# AIRZAI_LED_SENSE_FLEX_REVA.net
KiCad netlist of a schematic drawn in Altium Designer
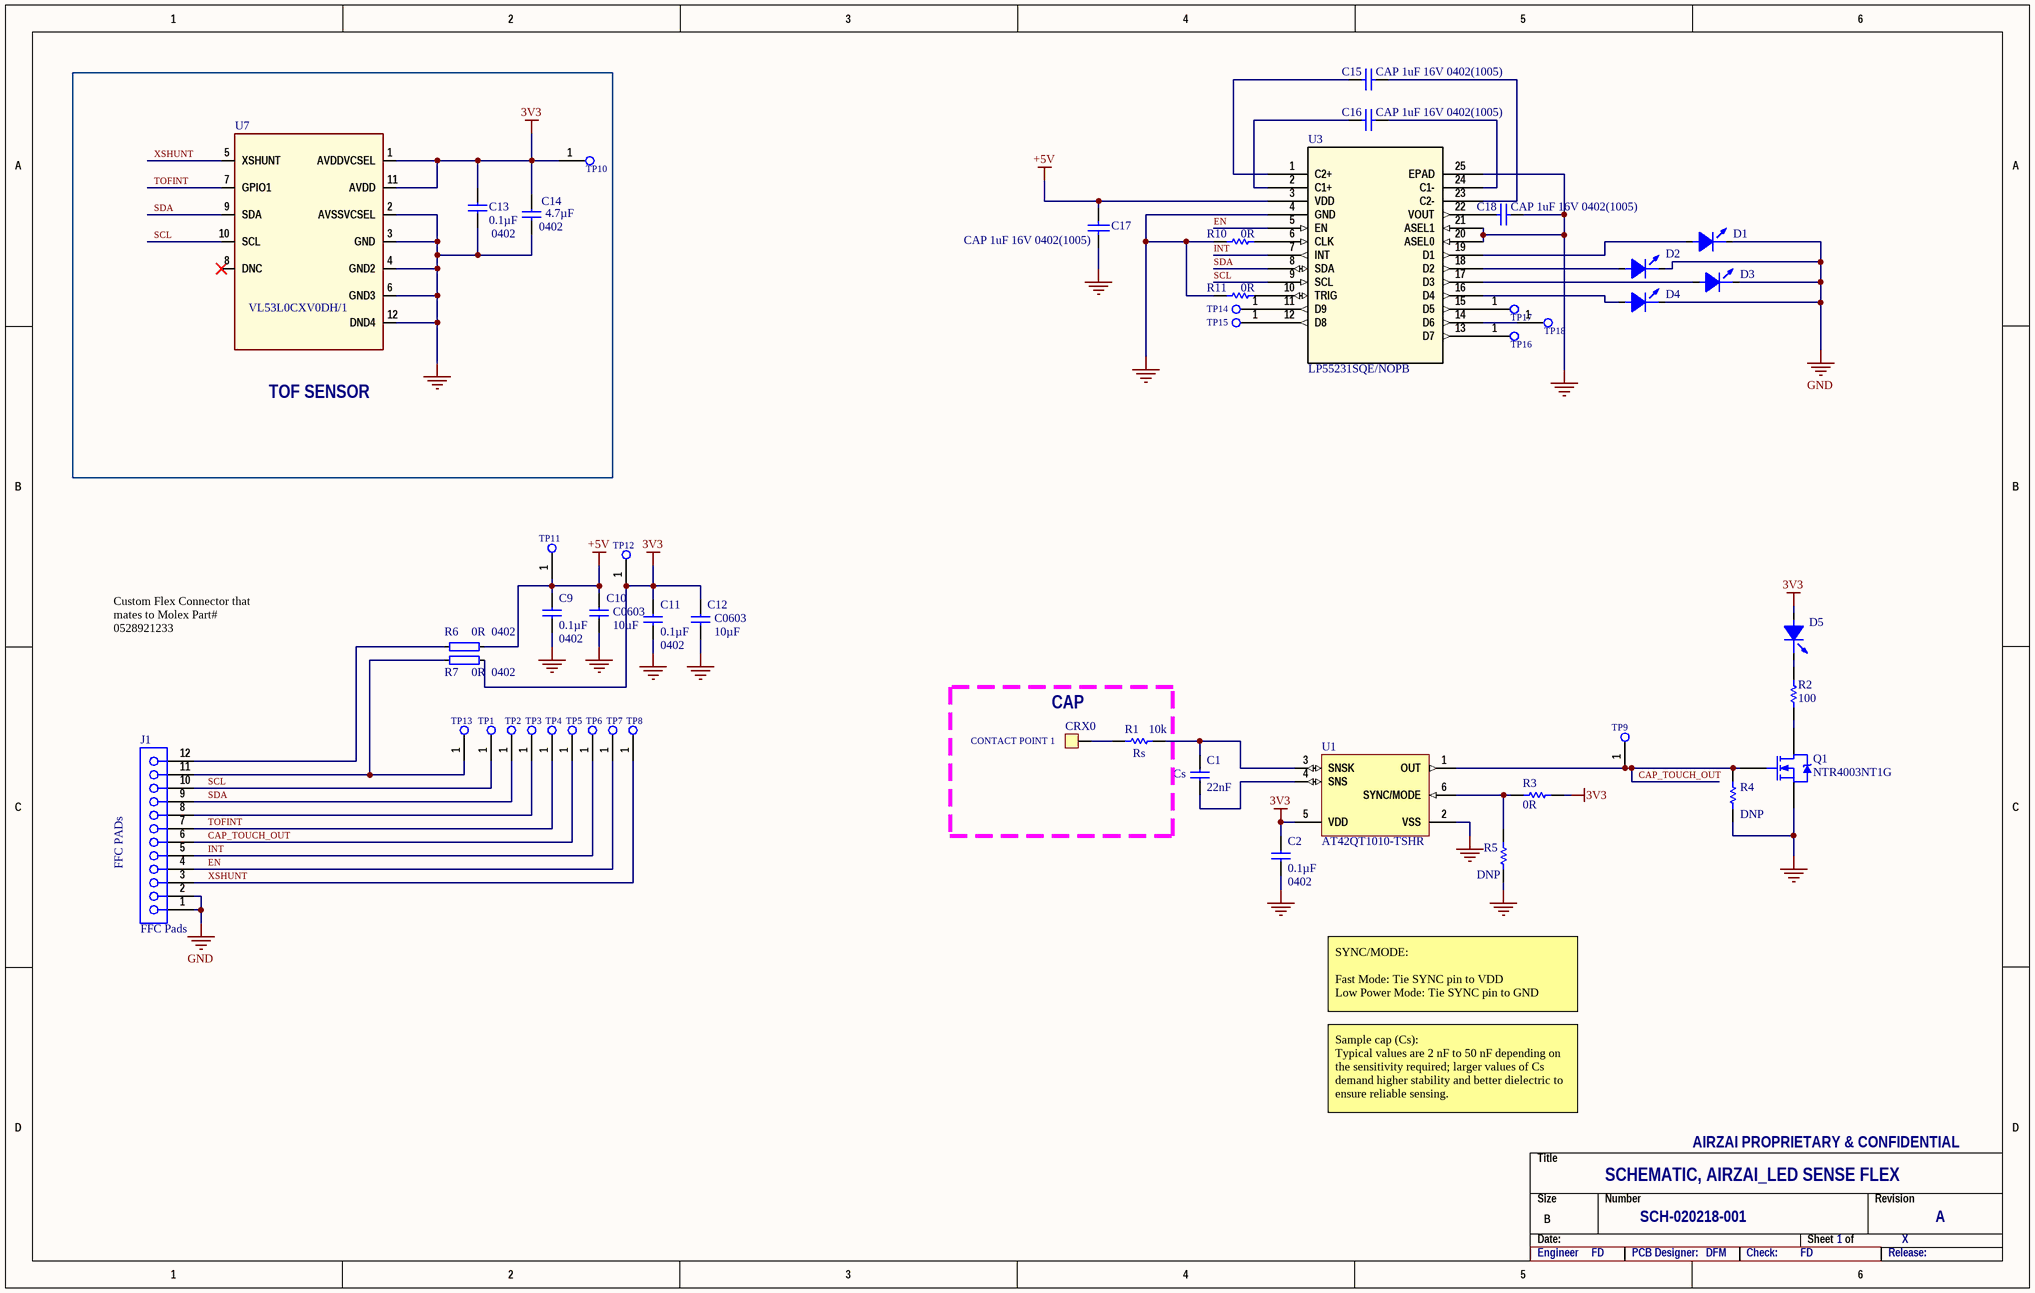
[diagram p0: AIRZAI_LED_SENSE_FLEX_REVA.SchDoc]

(export (version "E")
  (design (tool "Eeschema 10.0.6"))
  (components
    (comp (ref "C1")
      (value "22nF")
      (footprint "0402CAP")
      (description "Capacitor, X7R, ±10%")
      (fields
        (field (name "MANUFACTURER") "TDK")
        (field (name "MANUFACTURER PART NUMBER") "CGA2B2X7R1E223K050BA")
      )
      (libsource (lib "Nordic Passive DB") (part "CAP"))
    )
    (comp (ref "C2")
      (value "0.1µF")
      (footprint "0402")
      (description "Capacitor, X7R, ±10%")
      (fields (field (name "MANUFACTURER") "TDK") (field (name "MANUFACTURER PART NUMBER") "C1005X7R1C104K"))
      (libsource (lib "Nordic Passive DB") (part "CAP"))
    )
    (comp (ref "C9")
      (value "0.1µF")
      (footprint "0402")
      (description "Capacitor, X7R, ±10%")
      (fields (field (name "MANUFACTURER") "TDK") (field (name "MANUFACTURER PART NUMBER") "C1005X7R1C104K"))
      (libsource (lib "Nordic Passive DB") (part "CAP"))
    )
    (comp (ref "C10")
      (value "10µF")
      (footprint "C0603")
      (description "Capacitor, X7R, ±10%")
      (fields
        (field (name "MANUFACTURER") "MURATA")
        (field (name "MANUFACTURER PART NUMBER") "GRM188R60J106ME47D")
      )
      (libsource (lib "Nordic Passive DB") (part "CAP"))
    )
    (comp (ref "C11")
      (value "0.1µF")
      (footprint "0402")
      (description "Capacitor, X7R, ±10%")
      (fields (field (name "MANUFACTURER") "TDK") (field (name "MANUFACTURER PART NUMBER") "C1005X7R1C104K"))
      (libsource (lib "Nordic Passive DB") (part "CAP"))
    )
    (comp (ref "C12")
      (value "10µF")
      (footprint "C0603")
      (description "Capacitor, X7R, ±10%")
      (fields
        (field (name "MANUFACTURER") "MURATA")
        (field (name "MANUFACTURER PART NUMBER") "GRM188R60J106ME47D")
      )
      (libsource (lib "Nordic Passive DB") (part "CAP"))
    )
    (comp (ref "C13")
      (value "0.1µF")
      (footprint "0402")
      (description "Capacitor, X7R, ±10%")
      (fields (field (name "MANUFACTURER") "TDK") (field (name "MANUFACTURER PART NUMBER") "C1005X7R1C104K"))
      (libsource (lib "Nordic Passive DB") (part "CAP"))
    )
    (comp (ref "C14")
      (value "4.7µF")
      (footprint "0402")
      (description "Capacitor, X7R, ±10%")
      (fields (field (name "MANUFACTURER") "TDK") (field (name "MANUFACTURER PART NUMBER") "C1005X5R0J475M"))
      (libsource (lib "Nordic Passive DB") (part "CAP"))
    )
    (comp (ref "C15")
      (value "CAP 1uF 16V 0402(1005)")
      (footprint "CAPC0402(1005)60_M")
      (description "CAP 1uF 16V ±10% 0402 (1005 Metric) Thickness 0.6mm SMD")
      (fields (field (name "TOLERANCE") "Â±10%") (field (name "MANUFACTURER") "Taiyo Yuden"))
      (libsource (lib "AIRZAI_LED_SENSE_FLEX_REVA") (part "CAP"))
    )
    (comp (ref "C16")
      (value "CAP 1uF 16V 0402(1005)")
      (footprint "CAPC0402(1005)60_M")
      (description "CAP 1uF 16V ±10% 0402 (1005 Metric) Thickness 0.6mm SMD")
      (fields (field (name "TOLERANCE") "Â±10%") (field (name "MANUFACTURER") "Taiyo Yuden"))
      (libsource (lib "AIRZAI_LED_SENSE_FLEX_REVA") (part "CAP"))
    )
    (comp (ref "C17")
      (value "CAP 1uF 16V 0402(1005)")
      (footprint "CAPC0402(1005)60_M")
      (description "CAP 1uF 16V ±10% 0402 (1005 Metric) Thickness 0.6mm SMD")
      (fields (field (name "TOLERANCE") "Â±10%") (field (name "MANUFACTURER") "Taiyo Yuden"))
      (libsource (lib "AIRZAI_LED_SENSE_FLEX_REVA") (part "CAP"))
    )
    (comp (ref "C18")
      (value "CAP 1uF 16V 0402(1005)")
      (footprint "CAPC0402(1005)60_M")
      (description "CAP 1uF 16V ±10% 0402 (1005 Metric) Thickness 0.6mm SMD")
      (fields (field (name "TOLERANCE") "Â±10%") (field (name "MANUFACTURER") "Taiyo Yuden"))
      (libsource (lib "AIRZAI_LED_SENSE_FLEX_REVA") (part "CAP"))
    )
    (comp (ref "CRX0")
      (value "CONTACT POINT 1")
      (footprint "CONTACT_POINT_1CM _SQ")
      (libsource (lib "AIRZAI_LED_SENSE_FLEX_REVA") (part "WIRE_POINT"))
    )
    (comp (ref "D1")
      (value "WHITE")
      (footprint "LED1206_LTW-C230DS")
      (fields (field (name "MANUFACTURER PART NUMBER") "LTW-C230DS") (field (name "MANUFACTURER") "LITEON"))
      (libsource (lib "AIRZAI_LED_SENSE_FLEX_REVA") (part "LED_LTW-C230DS"))
    )
    (comp (ref "D2")
      (value "WHITE")
      (footprint "LED1206_LTW-C230DS")
      (fields (field (name "MANUFACTURER PART NUMBER") "LTW-C230DS") (field (name "MANUFACTURER") "LITEON"))
      (libsource (lib "AIRZAI_LED_SENSE_FLEX_REVA") (part "LED_LTW-C230DS"))
    )
    (comp (ref "D3")
      (value "WHITE")
      (footprint "LED1206_LTW-C230DS")
      (fields (field (name "MANUFACTURER PART NUMBER") "LTW-C230DS") (field (name "MANUFACTURER") "LITEON"))
      (libsource (lib "AIRZAI_LED_SENSE_FLEX_REVA") (part "LED_LTW-C230DS"))
    )
    (comp (ref "D4")
      (value "WHITE")
      (footprint "LED1206_LTW-C230DS")
      (fields (field (name "MANUFACTURER PART NUMBER") "LTW-C230DS") (field (name "MANUFACTURER") "LITEON"))
      (libsource (lib "AIRZAI_LED_SENSE_FLEX_REVA") (part "LED_LTW-C230DS"))
    )
    (comp (ref "D5")
      (value "WHITE")
      (footprint "LED1206_LTW-C230DS")
      (fields (field (name "MANUFACTURER PART NUMBER") "LTW-C230DS") (field (name "MANUFACTURER") "LITEON"))
      (libsource (lib "AIRZAI_LED_SENSE_FLEX_REVA") (part "LED_LTW-C230DS"))
    )
    (comp (ref "J1")
      (value "FFC Pads")
      (footprint "FFC_Pads")
      (description "0.5 mm Pitch FFC Pads")
      (libsource (lib "AIRZAI_LED_SENSE_FLEX_REVA") (part "FFC_PADS"))
    )
    (comp (ref "Q1")
      (value "NTR4003NT1G")
      (footprint "TO-220AB")
      (description "MOSFET N-CH 30V 500MA SOT-23")
      (fields (field (name "MANUFACTURER") "ON Semiconductor"))
      (libsource (lib "Miscellaneous Devices") (part "NMOS-2"))
    )
    (comp (ref "R1")
      (value "10k")
      (footprint "0402")
      (description "10k 0.063W 1% 0402 (1005 Metric)  SMD")
      (fields (field (name "TOLERANCE") "None") (field (name "POWER") "0.063W"))
      (libsource (lib "AIRZAI_LED_SENSE_FLEX_REVA") (part "RES"))
    )
    (comp (ref "R2")
      (value "100")
      (footprint "0402")
      (description "100 0.063W 1% 0402 (1005 Metric)  SMD")
      (fields (field (name "TOLERANCE") "None") (field (name "MANUFACTURER") "Yageo"))
      (libsource (lib "AIRZAI_LED_SENSE_FLEX_REVA") (part "RES"))
    )
    (comp (ref "R3")
      (value "0R")
      (footprint "0402")
      (description "Jumper 0402 (1005 Metric)")
      (fields (field (name "TOLERANCE") "None") (field (name "MANUFACTURER") "Panasonic"))
      (libsource (lib "AIRZAI_LED_SENSE_FLEX_REVA") (part "RES"))
    )
    (comp (ref "R4")
      (value "DNP")
      (footprint "0402")
      (fields
        (field (name "TOLERANCE") "None")
        (field (name "POWER") "0.0625 W")
        (field (name "Comment") "DNP 0402(1005)")
      )
      (libsource (lib "AIRZAI_LED_SENSE_FLEX_REVA") (part "RES"))
    )
    (comp (ref "R5")
      (value "DNP")
      (footprint "0402")
      (fields
        (field (name "TOLERANCE") "None")
        (field (name "POWER") "0.0625 W")
        (field (name "Comment") "DNP 0402(1005)")
      )
      (libsource (lib "AIRZAI_LED_SENSE_FLEX_REVA") (part "RES"))
    )
    (comp (ref "R6")
      (value "0R")
      (footprint "0402")
      (description "Resistor, ±1%, 0.063W")
      (fields
        (field (name "MANUFACTURER") "Panasonic")
        (field (name "MANUFACTURER PART NUMBER") "ERJ-2GE0R00X")
      )
      (libsource (lib "Nordic Passive DB") (part "RES_1"))
    )
    (comp (ref "R7")
      (value "0R")
      (footprint "0402")
      (description "Resistor, ±1%, 0.063W")
      (fields
        (field (name "MANUFACTURER") "Panasonic")
        (field (name "MANUFACTURER PART NUMBER") "ERJ-2GE0R00X")
      )
      (libsource (lib "Nordic Passive DB") (part "RES_1"))
    )
    (comp (ref "R10")
      (value "0R")
      (footprint "0402")
      (description "Jumper 0402 (1005 Metric)")
      (fields (field (name "TOLERANCE") "None") (field (name "MANUFACTURER") "Panasonic"))
      (libsource (lib "AIRZAI_LED_SENSE_FLEX_REVA") (part "RES"))
    )
    (comp (ref "R11")
      (value "0R")
      (footprint "0402")
      (description "Jumper 0402 (1005 Metric)")
      (fields (field (name "TOLERANCE") "None") (field (name "MANUFACTURER") "Panasonic"))
      (libsource (lib "AIRZAI_LED_SENSE_FLEX_REVA") (part "RES"))
    )
    (comp (ref "TP1")
      (value "Test Point")
      (footprint "TP_0.9MM")
      (libsource (lib "AIRZAI_LED_SENSE_FLEX_REVA") (part "Test Point"))
    )
    (comp (ref "TP2")
      (value "Test Point")
      (footprint "TP_0.9MM")
      (libsource (lib "AIRZAI_LED_SENSE_FLEX_REVA") (part "Test Point"))
    )
    (comp (ref "TP3")
      (value "Test Point")
      (footprint "TP_0.9MM")
      (libsource (lib "AIRZAI_LED_SENSE_FLEX_REVA") (part "Test Point"))
    )
    (comp (ref "TP4")
      (value "Test Point")
      (footprint "TP_0.9MM")
      (libsource (lib "AIRZAI_LED_SENSE_FLEX_REVA") (part "Test Point"))
    )
    (comp (ref "TP5")
      (value "Test Point")
      (footprint "TP_0.9MM")
      (libsource (lib "AIRZAI_LED_SENSE_FLEX_REVA") (part "Test Point"))
    )
    (comp (ref "TP6")
      (value "Test Point")
      (footprint "TP_0.9MM")
      (libsource (lib "AIRZAI_LED_SENSE_FLEX_REVA") (part "Test Point"))
    )
    (comp (ref "TP7")
      (value "Test Point")
      (footprint "TP_0.9MM")
      (libsource (lib "AIRZAI_LED_SENSE_FLEX_REVA") (part "Test Point"))
    )
    (comp (ref "TP8")
      (value "Test Point")
      (footprint "TP_0.9MM")
      (libsource (lib "AIRZAI_LED_SENSE_FLEX_REVA") (part "Test Point"))
    )
    (comp (ref "TP9")
      (value "Test Point")
      (footprint "TP_0.9MM")
      (libsource (lib "AIRZAI_LED_SENSE_FLEX_REVA") (part "Test Point"))
    )
    (comp (ref "TP10")
      (value "Test Point")
      (footprint "TP_0.9MM")
      (libsource (lib "AIRZAI_LED_SENSE_FLEX_REVA") (part "Test Point"))
    )
    (comp (ref "TP11")
      (value "Test Point")
      (footprint "TP_0.9MM")
      (libsource (lib "AIRZAI_LED_SENSE_FLEX_REVA") (part "Test Point"))
    )
    (comp (ref "TP12")
      (value "Test Point")
      (footprint "TP_0.9MM")
      (libsource (lib "AIRZAI_LED_SENSE_FLEX_REVA") (part "Test Point"))
    )
    (comp (ref "TP13")
      (value "Test Point")
      (footprint "TP_0.9MM")
      (libsource (lib "AIRZAI_LED_SENSE_FLEX_REVA") (part "Test Point"))
    )
    (comp (ref "TP14")
      (value "Test Point")
      (footprint "TP_0.9MM")
      (libsource (lib "AIRZAI_LED_SENSE_FLEX_REVA") (part "Test Point"))
    )
    (comp (ref "TP15")
      (value "Test Point")
      (footprint "TP_0.9MM")
      (libsource (lib "AIRZAI_LED_SENSE_FLEX_REVA") (part "Test Point"))
    )
    (comp (ref "TP16")
      (value "Test Point")
      (footprint "TP_0.9MM")
      (libsource (lib "AIRZAI_LED_SENSE_FLEX_REVA") (part "Test Point"))
    )
    (comp (ref "TP17")
      (value "Test Point")
      (footprint "TP_0.9MM")
      (libsource (lib "AIRZAI_LED_SENSE_FLEX_REVA") (part "Test Point"))
    )
    (comp (ref "TP18")
      (value "Test Point")
      (footprint "TP_0.9MM")
      (libsource (lib "AIRZAI_LED_SENSE_FLEX_REVA") (part "Test Point"))
    )
    (comp (ref "U1")
      (value "AT42QT1010-TSHR")
      (footprint "SOT-23-6-AT42QT1010-TSHR")
      (description "One-channel Touch Sensor IC with Reset Timer, -40° to +85° C, 6-pin SOT23")
      (libsource (lib "AIRZAI_LED_SENSE_FLEX_REVA") (part "AT42QT1010-TSHR"))
    )
    (comp (ref "U3")
      (value "LP55231SQE/NOPB")
      (footprint "WQFN-24-LP55231SQE/NOPB")
      (description "Imported")
      (fields (field (name "MANUFACTURER") "TI") (field (name "TOLERANCE") "None"))
      (libsource (lib "AltiumDesigner") (part "LP55231SQE/NOPB"))
    )
    (comp (ref "U7")
      (value "VL53L0CXV0DH/1")
      (footprint "VL53L0X")
      (fields (field (name "MANUFACTURER") "ST") (field (name "TOLERANCE") "None"))
      (libsource (lib "DFM_JBKEGSVS_Library") (part "VL53L0X"))
    )
  )
  (nets
    (net (code "1") (name "+5V") (class "Default")
      (node (ref "C10") (pin "1") (pinfunction "1_1") (pintype "passive"))
      (node (ref "C17") (pin "2") (pinfunction "2_2") (pintype "passive"))
      (node (ref "C9") (pin "1") (pinfunction "1_1") (pintype "passive"))
      (node (ref "R6") (pin "1") (pinfunction "1_1") (pintype "passive"))
      (node (ref "TP11") (pin "1") (pinfunction "1_1") (pintype "passive"))
      (node (ref "U3") (pin "3") (pinfunction "VDD_3") (pintype "power_in"))
    )
    (net (code "2") (name "/CAP_TOUCH_OUT") (class "Default")
      (node (ref "J1") (pin "6") (pinfunction "6_6") (pintype "passive"))
      (node (ref "Q1") (pin "1") (pinfunction "G_1") (pintype "passive"))
      (node (ref "R4") (pin "1") (pinfunction "1_1") (pintype "passive"))
      (node (ref "TP5") (pin "1") (pinfunction "1_1") (pintype "passive"))
      (node (ref "TP9") (pin "1") (pinfunction "1_1") (pintype "passive"))
      (node (ref "U1") (pin "1") (pinfunction "OUT_1") (pintype "output"))
    )
    (net (code "3") (name "/EN") (class "Default")
      (node (ref "J1") (pin "4") (pinfunction "4_4") (pintype "passive"))
      (node (ref "TP7") (pin "1") (pinfunction "1_1") (pintype "passive"))
      (node (ref "U3") (pin "5") (pinfunction "EN_5") (pintype "input"))
    )
    (net (code "4") (name "/INT") (class "Default")
      (node (ref "J1") (pin "5") (pinfunction "5_5") (pintype "passive"))
      (node (ref "TP6") (pin "1") (pinfunction "1_1") (pintype "passive"))
      (node (ref "U3") (pin "7") (pinfunction "INT_7") (pintype "output"))
    )
    (net (code "5") (name "/SCL") (class "Default")
      (node (ref "J1") (pin "10") (pinfunction "10_10") (pintype "passive"))
      (node (ref "TP1") (pin "1") (pinfunction "1_1") (pintype "passive"))
      (node (ref "U3") (pin "9") (pinfunction "SCL_9") (pintype "input"))
      (node (ref "U7") (pin "10") (pinfunction "SCL_10") (pintype "passive"))
    )
    (net (code "6") (name "/SDA") (class "Default")
      (node (ref "J1") (pin "9") (pinfunction "9_9") (pintype "passive"))
      (node (ref "TP2") (pin "1") (pinfunction "1_1") (pintype "passive"))
      (node (ref "U3") (pin "8") (pinfunction "SDA_8") (pintype "bidirectional"))
      (node (ref "U7") (pin "9") (pinfunction "SDA_9") (pintype "passive"))
    )
    (net (code "7") (name "/TOFINT") (class "Default")
      (node (ref "J1") (pin "7") (pinfunction "7_7") (pintype "passive"))
      (node (ref "TP4") (pin "1") (pinfunction "1_1") (pintype "passive"))
      (node (ref "U7") (pin "7") (pinfunction "GPIO1_7") (pintype "passive"))
    )
    (net (code "8") (name "/XSHUNT") (class "Default")
      (node (ref "J1") (pin "3") (pinfunction "3_3") (pintype "passive"))
      (node (ref "TP8") (pin "1") (pinfunction "1_1") (pintype "passive"))
      (node (ref "U7") (pin "5") (pinfunction "XSHUNT_5") (pintype "passive"))
    )
    (net (code "9") (name "3V3") (class "Default")
      (node (ref "C11") (pin "1") (pinfunction "1_1") (pintype "passive"))
      (node (ref "C12") (pin "1") (pinfunction "1_1") (pintype "passive"))
      (node (ref "C13") (pin "1") (pinfunction "1_1") (pintype "passive"))
      (node (ref "C14") (pin "2") (pinfunction "2_2") (pintype "passive"))
      (node (ref "C2") (pin "1") (pinfunction "1_1") (pintype "passive"))
      (node (ref "D5") (pin "2") (pinfunction "ANODE_2") (pintype "passive"))
      (node (ref "R3") (pin "2") (pinfunction "2_2") (pintype "passive"))
      (node (ref "R7") (pin "1") (pinfunction "1_1") (pintype "passive"))
      (node (ref "TP10") (pin "1") (pinfunction "1_1") (pintype "passive"))
      (node (ref "TP12") (pin "1") (pinfunction "1_1") (pintype "passive"))
      (node (ref "U1") (pin "5") (pinfunction "VDD_5") (pintype "power_in"))
      (node (ref "U7") (pin "1") (pinfunction "AVDDVCSEL_1") (pintype "passive"))
      (node (ref "U7") (pin "11") (pinfunction "AVDD_11") (pintype "passive"))
    )
    (net (code "10") (name "GND") (class "Default")
      (node (ref "C10") (pin "2") (pinfunction "2_2") (pintype "passive"))
      (node (ref "C11") (pin "2") (pinfunction "2_2") (pintype "passive"))
      (node (ref "C12") (pin "2") (pinfunction "2_2") (pintype "passive"))
      (node (ref "C13") (pin "2") (pinfunction "2_2") (pintype "passive"))
      (node (ref "C14") (pin "1") (pinfunction "1_1") (pintype "passive"))
      (node (ref "C17") (pin "1") (pinfunction "1_1") (pintype "passive"))
      (node (ref "C18") (pin "2") (pinfunction "2_2") (pintype "passive"))
      (node (ref "C2") (pin "2") (pinfunction "2_2") (pintype "passive"))
      (node (ref "C9") (pin "2") (pinfunction "2_2") (pintype "passive"))
      (node (ref "D1") (pin "1") (pinfunction "CATHODE_1") (pintype "passive"))
      (node (ref "D2") (pin "1") (pinfunction "CATHODE_1") (pintype "passive"))
      (node (ref "D3") (pin "1") (pinfunction "CATHODE_1") (pintype "passive"))
      (node (ref "D4") (pin "1") (pinfunction "CATHODE_1") (pintype "passive"))
      (node (ref "J1") (pin "1") (pinfunction "1_1") (pintype "passive"))
      (node (ref "J1") (pin "2") (pinfunction "2_2") (pintype "passive"))
      (node (ref "Q1") (pin "3") (pinfunction "S_3") (pintype "passive"))
      (node (ref "R10") (pin "1") (pinfunction "1_1") (pintype "passive"))
      (node (ref "R11") (pin "1") (pinfunction "1_1") (pintype "passive"))
      (node (ref "R4") (pin "2") (pinfunction "2_2") (pintype "passive"))
      (node (ref "R5") (pin "2") (pinfunction "2_2") (pintype "passive"))
      (node (ref "U1") (pin "2") (pinfunction "VSS_2") (pintype "power_in"))
      (node (ref "U3") (pin "20") (pinfunction "ASEL0_20") (pintype "input"))
      (node (ref "U3") (pin "21") (pinfunction "ASEL1_21") (pintype "input"))
      (node (ref "U3") (pin "25") (pinfunction "EPAD_25") (pintype "passive"))
      (node (ref "U3") (pin "4") (pinfunction "GND_4") (pintype "power_in"))
      (node (ref "U7") (pin "12") (pinfunction "DND4_12") (pintype "passive"))
      (node (ref "U7") (pin "2") (pinfunction "AVSSVCSEL_2") (pintype "passive"))
      (node (ref "U7") (pin "3") (pinfunction "GND_3") (pintype "passive"))
      (node (ref "U7") (pin "4") (pinfunction "GND2_4") (pintype "passive"))
      (node (ref "U7") (pin "6") (pinfunction "GND3_6") (pintype "passive"))
    )
    (net (code "11") (name "Net-(CRX0-Pad1)") (class "Default")
      (node (ref "CRX0") (pin "1") (pinfunction "1_1") (pintype "passive"))
      (node (ref "R1") (pin "2") (pinfunction "2_2") (pintype "passive"))
    )
    (net (code "12") (name "Net-(D1-ANODE)") (class "Default")
      (node (ref "D1") (pin "2") (pinfunction "ANODE_2") (pintype "passive"))
      (node (ref "U3") (pin "19") (pinfunction "D1_19") (pintype "output"))
    )
    (net (code "13") (name "Net-(D2-ANODE)") (class "Default")
      (node (ref "D2") (pin "2") (pinfunction "ANODE_2") (pintype "passive"))
      (node (ref "U3") (pin "18") (pinfunction "D2_18") (pintype "output"))
    )
    (net (code "14") (name "Net-(D3-ANODE)") (class "Default")
      (node (ref "D3") (pin "2") (pinfunction "ANODE_2") (pintype "passive"))
      (node (ref "U3") (pin "17") (pinfunction "D3_17") (pintype "output"))
    )
    (net (code "15") (name "Net-(D4-ANODE)") (class "Default")
      (node (ref "D4") (pin "2") (pinfunction "ANODE_2") (pintype "passive"))
      (node (ref "U3") (pin "16") (pinfunction "D4_16") (pintype "output"))
    )
    (net (code "16") (name "Net-(D5-CATHODE)") (class "Default")
      (node (ref "D5") (pin "1") (pinfunction "CATHODE_1") (pintype "passive"))
      (node (ref "R2") (pin "2") (pinfunction "2_2") (pintype "passive"))
    )
    (net (code "17") (name "Net-(J1-Pad8)") (class "Default")
      (node (ref "J1") (pin "8") (pinfunction "8_8") (pintype "passive"))
      (node (ref "TP3") (pin "1") (pinfunction "1_1") (pintype "passive"))
    )
    (net (code "18") (name "Net-(J1-Pad11)") (class "Default")
      (node (ref "J1") (pin "11") (pinfunction "11_11") (pintype "passive"))
      (node (ref "R7") (pin "2") (pinfunction "2_2") (pintype "passive"))
      (node (ref "TP13") (pin "1") (pinfunction "1_1") (pintype "passive"))
    )
    (net (code "19") (name "Net-(J1-Pad12)") (class "Default")
      (node (ref "J1") (pin "12") (pinfunction "12_12") (pintype "passive"))
      (node (ref "R6") (pin "2") (pinfunction "2_2") (pintype "passive"))
    )
    (net (code "20") (name "Net-(Q1-D)") (class "Default")
      (node (ref "Q1") (pin "2") (pinfunction "D_2") (pintype "passive"))
      (node (ref "R2") (pin "1") (pinfunction "1_1") (pintype "passive"))
    )
    (net (code "21") (name "Net-(U1-SNS)") (class "Default")
      (node (ref "C1") (pin "2") (pinfunction "2_2") (pintype "passive"))
      (node (ref "U1") (pin "4") (pinfunction "SNS_4") (pintype "bidirectional"))
    )
    (net (code "22") (name "Net-(U1-SNSK)") (class "Default")
      (node (ref "C1") (pin "1") (pinfunction "1_1") (pintype "passive"))
      (node (ref "R1") (pin "1") (pinfunction "1_1") (pintype "passive"))
      (node (ref "U1") (pin "3") (pinfunction "SNSK_3") (pintype "bidirectional"))
    )
    (net (code "23") (name "Net-(U1-SYNC{slash}MODE)") (class "Default")
      (node (ref "R3") (pin "1") (pinfunction "1_1") (pintype "passive"))
      (node (ref "R5") (pin "1") (pinfunction "1_1") (pintype "passive"))
      (node (ref "U1") (pin "6") (pinfunction "SYNC/MODE_6") (pintype "input"))
    )
    (net (code "24") (name "Net-(U3-C1+)") (class "Default")
      (node (ref "C16") (pin "1") (pinfunction "1_1") (pintype "passive"))
      (node (ref "U3") (pin "2") (pinfunction "C1+_2") (pintype "passive"))
    )
    (net (code "25") (name "Net-(U3-C1-)") (class "Default")
      (node (ref "C16") (pin "2") (pinfunction "2_2") (pintype "passive"))
      (node (ref "U3") (pin "24") (pinfunction "C1-_24") (pintype "passive"))
    )
    (net (code "26") (name "Net-(U3-C2+)") (class "Default")
      (node (ref "C15") (pin "1") (pinfunction "1_1") (pintype "passive"))
      (node (ref "U3") (pin "1") (pinfunction "C2+_1") (pintype "passive"))
    )
    (net (code "27") (name "Net-(U3-C2-)") (class "Default")
      (node (ref "C15") (pin "2") (pinfunction "2_2") (pintype "passive"))
      (node (ref "U3") (pin "23") (pinfunction "C2-_23") (pintype "passive"))
    )
    (net (code "28") (name "Net-(U3-CLK)") (class "Default")
      (node (ref "R10") (pin "2") (pinfunction "2_2") (pintype "passive"))
      (node (ref "U3") (pin "6") (pinfunction "CLK_6") (pintype "input"))
    )
    (net (code "29") (name "Net-(U3-D5)") (class "Default")
      (node (ref "TP17") (pin "1") (pinfunction "1_1") (pintype "passive"))
      (node (ref "U3") (pin "15") (pinfunction "D5_15") (pintype "output"))
    )
    (net (code "30") (name "Net-(U3-D6)") (class "Default")
      (node (ref "TP18") (pin "1") (pinfunction "1_1") (pintype "passive"))
      (node (ref "U3") (pin "14") (pinfunction "D6_14") (pintype "output"))
    )
    (net (code "31") (name "Net-(U3-D7)") (class "Default")
      (node (ref "TP16") (pin "1") (pinfunction "1_1") (pintype "passive"))
      (node (ref "U3") (pin "13") (pinfunction "D7_13") (pintype "output"))
    )
    (net (code "32") (name "Net-(U3-D8)") (class "Default")
      (node (ref "TP15") (pin "1") (pinfunction "1_1") (pintype "passive"))
      (node (ref "U3") (pin "12") (pinfunction "D8_12") (pintype "output"))
    )
    (net (code "33") (name "Net-(U3-D9)") (class "Default")
      (node (ref "TP14") (pin "1") (pinfunction "1_1") (pintype "passive"))
      (node (ref "U3") (pin "11") (pinfunction "D9_11") (pintype "output"))
    )
    (net (code "34") (name "Net-(U3-TRIG)") (class "Default")
      (node (ref "R11") (pin "2") (pinfunction "2_2") (pintype "passive"))
      (node (ref "U3") (pin "10") (pinfunction "TRIG_10") (pintype "bidirectional"))
    )
    (net (code "35") (name "Net-(U3-VOUT)") (class "Default")
      (node (ref "C18") (pin "1") (pinfunction "1_1") (pintype "passive"))
      (node (ref "U3") (pin "22") (pinfunction "VOUT_22") (pintype "output"))
    )
    (net (code "36") (name "unconnected-(U7-DNC-Pad8)") (class "Default")
      (node (ref "U7") (pin "8") (pinfunction "DNC_8") (pintype "passive+no_connect"))
    )
  )
)
